# FreshPal_Schematic.net
KiCad netlist of a schematic drawn in Altium Designer
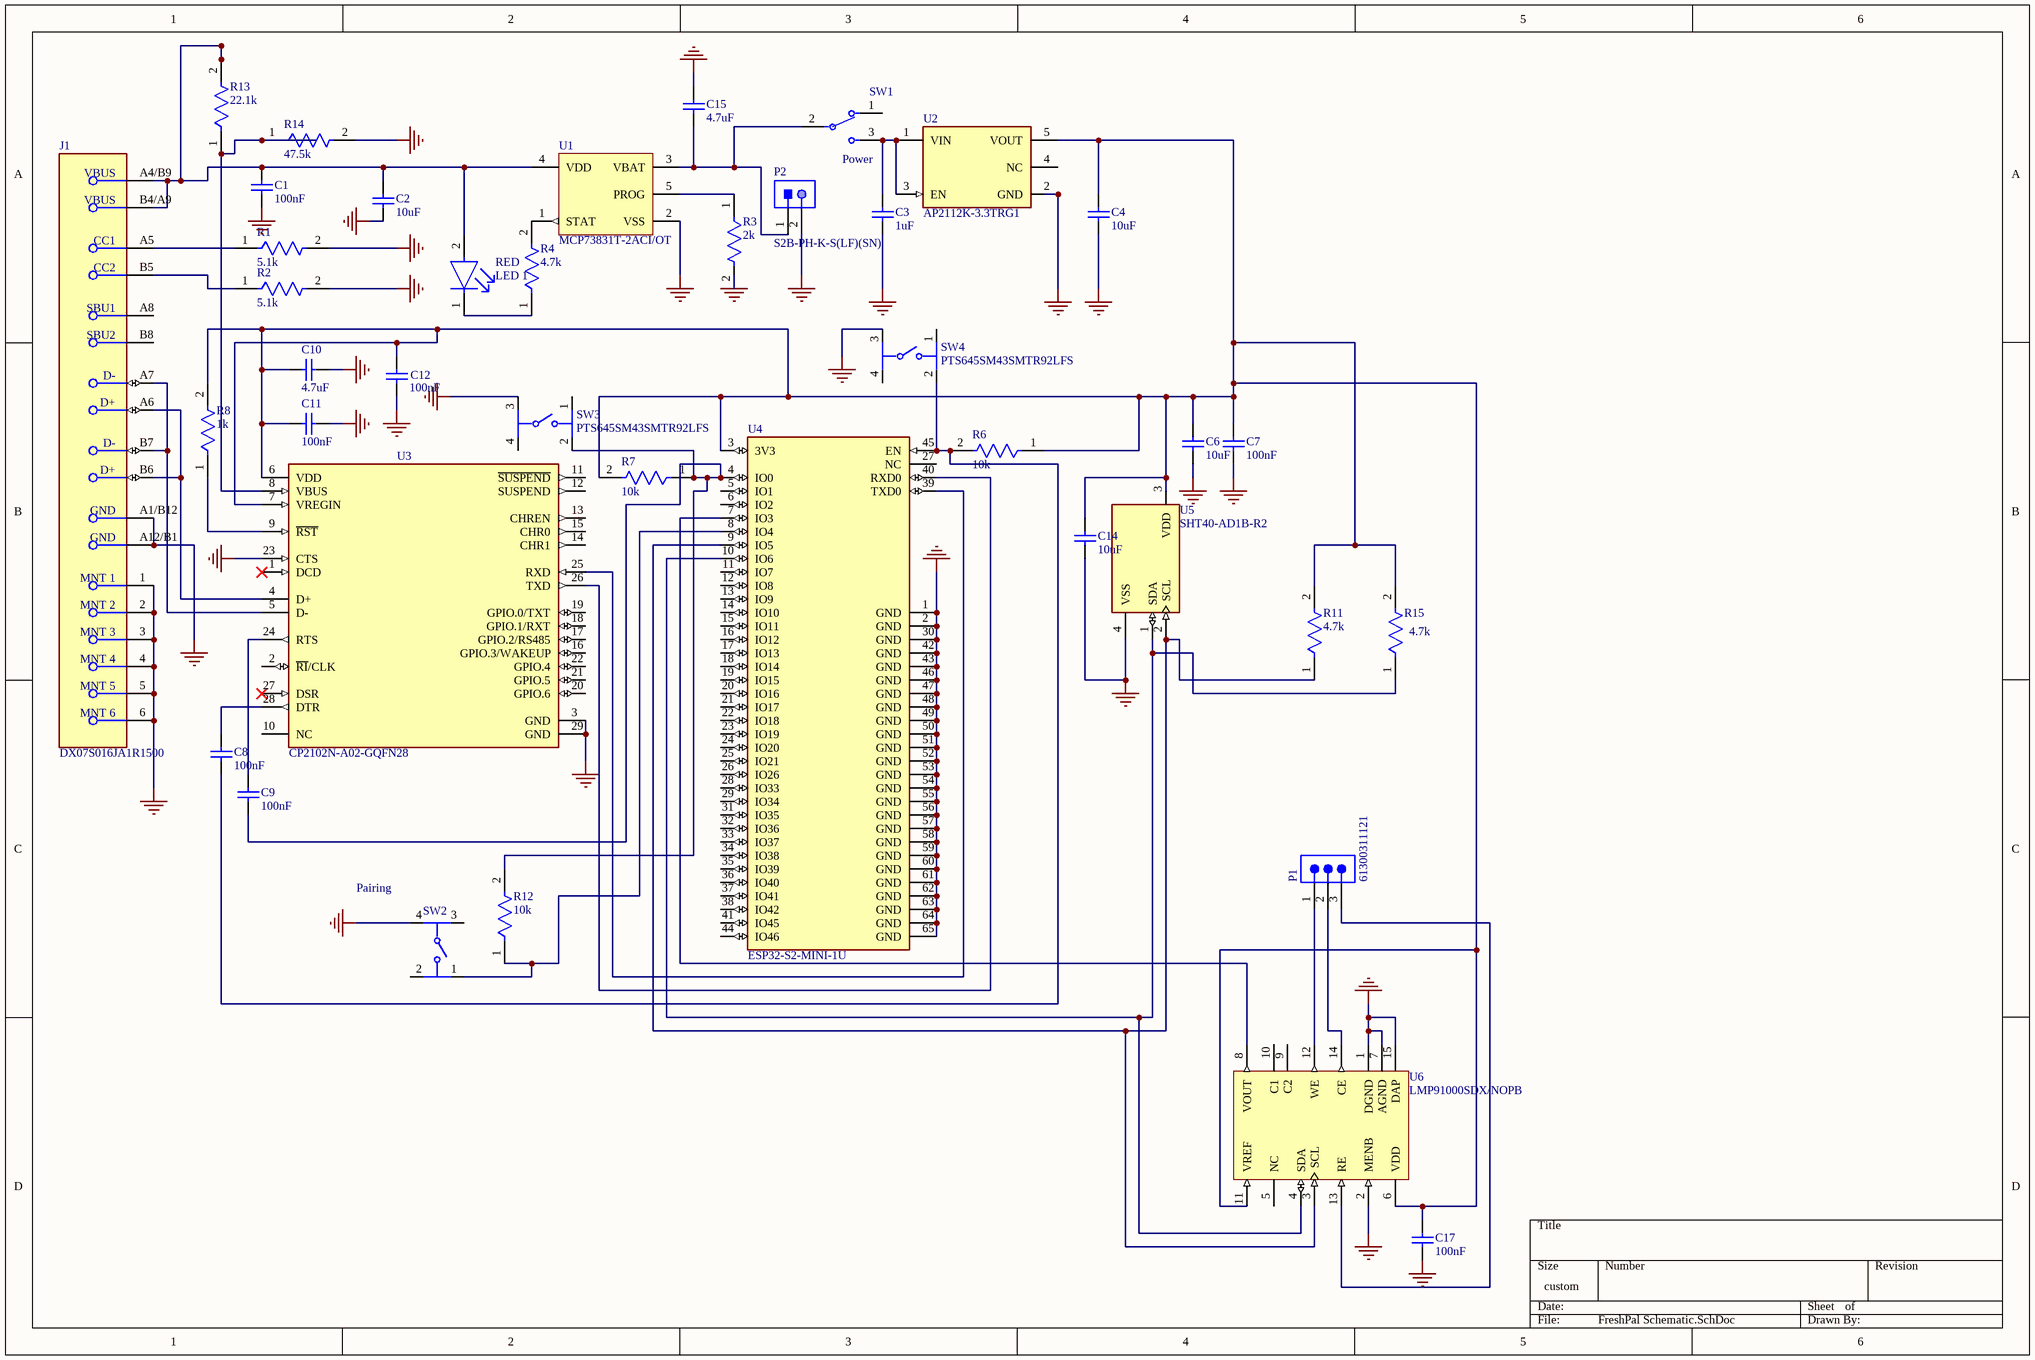
[diagram p0: FreshPal Schematic.SchDoc]

(export (version "E")
  (design (tool "Eeschema 10.0.6"))
  (components
    (comp (ref "C1")
      (value "100nF")
      (footprint "CAPC0603(1608)100_L")
      (description "CAP 3.3pF 16V ±0.1pF 0603 (1608 Metric) Thickness 1mm SMD")
      (fields (field (name "TOLERANCE") "Â±0.1pF"))
      (libsource (lib "Altium Content Vault") (part "CAP"))
    )
    (comp (ref "C2")
      (value "10uF")
      (footprint "CAPC0603(1608)100_L")
      (description "CAP 3.3pF 16V ±0.1pF 0603 (1608 Metric) Thickness 1mm SMD")
      (fields (field (name "TOLERANCE") "Â±0.1pF"))
      (libsource (lib "Altium Content Vault") (part "CAP"))
    )
    (comp (ref "C3")
      (value "1uF")
      (footprint "CAPC0603(1608)100_L")
      (description "CAP 3.3pF 16V ±0.1pF 0603 (1608 Metric) Thickness 1mm SMD")
      (fields (field (name "TOLERANCE") "Â±0.1pF"))
      (libsource (lib "Altium Content Vault") (part "CAP"))
    )
    (comp (ref "C4")
      (value "10uF")
      (footprint "CAPC0603(1608)100_L")
      (description "CAP 3.3pF 16V ±0.1pF 0603 (1608 Metric) Thickness 1mm SMD")
      (fields (field (name "TOLERANCE") "Â±0.1pF"))
      (libsource (lib "Altium Content Vault") (part "CAP"))
    )
    (comp (ref "C6")
      (value "10uF")
      (footprint "CAPC0603(1608)100_L")
      (description "CAP 3.3pF 16V ±0.1pF 0603 (1608 Metric) Thickness 1mm SMD")
      (fields (field (name "TOLERANCE") "Â±0.1pF"))
      (libsource (lib "Altium Content Vault") (part "CAP"))
    )
    (comp (ref "C7")
      (value "100nF")
      (footprint "CAPC0603(1608)100_L")
      (description "CAP 3.3pF 16V ±0.1pF 0603 (1608 Metric) Thickness 1mm SMD")
      (fields (field (name "TOLERANCE") "Â±0.1pF"))
      (libsource (lib "Altium Content Vault") (part "CAP"))
    )
    (comp (ref "C8")
      (value "100nF")
      (footprint "CAPC0603(1608)100_L")
      (description "CAP 3.3pF 16V ±0.1pF 0603 (1608 Metric) Thickness 1mm SMD")
      (fields (field (name "TOLERANCE") "Â±0.1pF"))
      (libsource (lib "Altium Content Vault") (part "CAP"))
    )
    (comp (ref "C9")
      (value "100nF")
      (footprint "CAPC0603(1608)100_L")
      (description "CAP 3.3pF 16V ±0.1pF 0603 (1608 Metric) Thickness 1mm SMD")
      (fields (field (name "TOLERANCE") "Â±0.1pF"))
      (libsource (lib "Altium Content Vault") (part "CAP"))
    )
    (comp (ref "C10")
      (value "4.7uF")
      (footprint "CAPC0603(1608)100_L")
      (description "CAP 3.3pF 16V ±0.1pF 0603 (1608 Metric) Thickness 1mm SMD")
      (fields (field (name "TOLERANCE") "Â±0.1pF"))
      (libsource (lib "Altium Content Vault") (part "CAP"))
    )
    (comp (ref "C11")
      (value "100nF")
      (footprint "CAPC0603(1608)100_L")
      (description "CAP 3.3pF 16V ±0.1pF 0603 (1608 Metric) Thickness 1mm SMD")
      (fields (field (name "TOLERANCE") "Â±0.1pF"))
      (libsource (lib "Altium Content Vault") (part "CAP"))
    )
    (comp (ref "C12")
      (value "100nF")
      (footprint "CAPC0603(1608)100_L")
      (description "CAP 3.3pF 16V ±0.1pF 0603 (1608 Metric) Thickness 1mm SMD")
      (fields (field (name "TOLERANCE") "Â±0.1pF"))
      (libsource (lib "Altium Content Vault") (part "CAP"))
    )
    (comp (ref "C14")
      (value "10uF")
      (footprint "CAPC0603(1608)100_L")
      (description "CAP 3.3pF 16V ±0.1pF 0603 (1608 Metric) Thickness 1mm SMD")
      (fields (field (name "TOLERANCE") "Â±0.1pF"))
      (libsource (lib "Altium Content Vault") (part "CAP"))
    )
    (comp (ref "C15")
      (value "4.7uF")
      (footprint "CAPC0603(1608)100_L")
      (description "CAP 3.3pF 16V ±0.1pF 0603 (1608 Metric) Thickness 1mm SMD")
      (fields (field (name "TOLERANCE") "Â±0.1pF"))
      (libsource (lib "Altium Content Vault") (part "CAP"))
    )
    (comp (ref "C17")
      (value "100nF")
      (footprint "CAPC0603(1608)100_L")
      (description "CAP 3.3pF 16V ±0.1pF 0603 (1608 Metric) Thickness 1mm SMD")
      (fields (field (name "TOLERANCE") "Â±0.1pF"))
      (libsource (lib "Altium Content Vault") (part "CAP"))
    )
    (comp (ref "J1")
      (value "DX07S016JA1R1500")
      (footprint "FP-DX07S016JA1R1500-MFG")
      (description "CONN RCP USB2.0 TYP C 24P SMD RA")
      (libsource (lib "Altium Content Vault") (part "7f3e9989102a0f22bff9cb010881d34"))
    )
    (comp (ref "P1")
      (value "61300311121")
      (footprint "61300311121")
      (description "THT Vertical Pin Header WR-PHD, Pitch 2.54 mm, Single Row, 3 pins")
      (libsource (lib "Altium Content Vault") (part "Header_Male_1R_03P"))
    )
    (comp (ref "P2")
      (value "S2B-PH-K-S(LF)(SN)")
      (footprint "JST-S2B-PH-K-S_V")
      (fields (field (name "TOLERANCE") "20%"))
      (libsource (lib "Altium Content Vault") (part "CN-1P-M-R2"))
    )
    (comp (ref "R1")
      (value "5.1k")
      (footprint "FP-RN73R1E-MFG")
      (description "5.1kΩ ±0.5% 0.063W, 1/16W Chip Resistor 0402 (1005 Metric) Moisture Resistant Thin Film")
      (libsource (lib "Altium Content Vault") (part "1029c3af85768c4190bb7ad29bc67b5"))
    )
    (comp (ref "R2")
      (value "5.1k")
      (footprint "FP-RN73R1E-MFG")
      (description "5.1kΩ ±0.5% 0.063W, 1/16W Chip Resistor 0402 (1005 Metric) Moisture Resistant Thin Film")
      (libsource (lib "Altium Content Vault") (part "1029c3af85768c4190bb7ad29bc67b5"))
    )
    (comp (ref "R3")
      (value "2k")
      (footprint "FP-RN73R1E-IPC_B")
      (description "2kΩ ±1% 0.063W, 1/16W Chip Resistor 0402 (1005 Metric) Moisture Resistant Thin Film")
      (libsource (lib "Altium Content Vault") (part "1029c3af85768c4190bb7ad29bc67b5"))
    )
    (comp (ref "R4")
      (value "4.7k")
      (footprint "FP-RN73R1E-MFG")
      (description "5.1kΩ ±0.5% 0.063W, 1/16W Chip Resistor 0402 (1005 Metric) Moisture Resistant Thin Film")
      (libsource (lib "Altium Content Vault") (part "1029c3af85768c4190bb7ad29bc67b5"))
    )
    (comp (ref "R6")
      (value "10k")
      (footprint "FP-RN73R1E-MFG")
      (description "5.1kΩ ±0.5% 0.063W, 1/16W Chip Resistor 0402 (1005 Metric) Moisture Resistant Thin Film")
      (libsource (lib "Altium Content Vault") (part "1029c3af85768c4190bb7ad29bc67b5"))
    )
    (comp (ref "R7")
      (value "10k")
      (footprint "FP-RN73R1E-MFG")
      (description "5.1kΩ ±0.5% 0.063W, 1/16W Chip Resistor 0402 (1005 Metric) Moisture Resistant Thin Film")
      (libsource (lib "Altium Content Vault") (part "1029c3af85768c4190bb7ad29bc67b5"))
    )
    (comp (ref "R8")
      (value "1k")
      (footprint "FP-RN73R1E-MFG")
      (description "5.1kΩ ±0.5% 0.063W, 1/16W Chip Resistor 0402 (1005 Metric) Moisture Resistant Thin Film")
      (libsource (lib "Altium Content Vault") (part "1029c3af85768c4190bb7ad29bc67b5"))
    )
    (comp (ref "R11")
      (value "4.7k")
      (footprint "FP-RN73R1E-MFG")
      (description "5.1kΩ ±0.5% 0.063W, 1/16W Chip Resistor 0402 (1005 Metric) Moisture Resistant Thin Film")
      (libsource (lib "Altium Content Vault") (part "1029c3af85768c4190bb7ad29bc67b5"))
    )
    (comp (ref "R12")
      (value "10k")
      (footprint "FP-RN73R1E-MFG")
      (description "5.1kΩ ±0.5% 0.063W, 1/16W Chip Resistor 0402 (1005 Metric) Moisture Resistant Thin Film")
      (libsource (lib "Altium Content Vault") (part "1029c3af85768c4190bb7ad29bc67b5"))
    )
    (comp (ref "R13")
      (value "22.1k")
      (footprint "FP-RN73R1E-MFG")
      (description "5.1kΩ ±0.5% 0.063W, 1/16W Chip Resistor 0402 (1005 Metric) Moisture Resistant Thin Film")
      (libsource (lib "Altium Content Vault") (part "1029c3af85768c4190bb7ad29bc67b5"))
    )
    (comp (ref "R14")
      (value "47.5k")
      (footprint "FP-RN732A-MFG")
      (description "SMD Chip Resistor, Thin Film, 69.8KΩ, 100 V, 0805 [2012 Metric], 100 mW, 0.1%, RN73 Series")
      (fields
        (field (name "OCTOPART") "https://octopart.com/rn73c2a69k8btdf-te+connectivity-42431909")
        (field (name "TOLERANCE") "0.1%")
      )
      (libsource (lib "Altium Content Vault") (part "1029c3af85768c4190bb7ad29bc67b5"))
    )
    (comp (ref "R15")
      (value "4.7k")
      (footprint "FP-RN73R1E-MFG")
      (description "5.1kΩ ±0.5% 0.063W, 1/16W Chip Resistor 0402 (1005 Metric) Moisture Resistant Thin Film")
      (libsource (lib "Altium Content Vault") (part "1029c3af85768c4190bb7ad29bc67b5"))
    )
    (comp (ref "RED")
      (value "LED 1")
      (footprint "FP-SML-P1-MFG")
      (description "LED RED CLEAR 1006 SMD")
      (fields
        (field (name "MANUFACTURER PART NUMBER") "SML-P11VTT86R")
        (field (name "OCTOPART") "https://octopart.com/sml-p11vtt86r-rohm-34112314")
      )
      (libsource (lib "Altium Content Vault") (part "8706943c75ba83719d021d2fdc84c58"))
    )
    (comp (ref "SW1")
      (value "S102011SCQN")
      (footprint "FP-JS102011SCQN-MFG")
      (description "SWITCH SLIDE SPDT 300MA 6V")
      (libsource (lib "Altium Content Vault") (part "39e195cbbadc85d1df0d7eb6847d379"))
    )
    (comp (ref "SW2")
      (value "~")
      (footprint "PTS645SM43SMTR92LFS_MFG")
      (description "Switch Tactile N.O SPST Round Button Gull Wing 0.05A 12VDC 100000Cycle 1.57N SMD T/R")
      (libsource (lib "Altium Content Vault") (part "e4f2503661fe04264f50fb928c13ad2"))
    )
    (comp (ref "SW3")
      (value "PTS645SM43SMTR92LFS")
      (footprint "PTS645SM43SMTR92LFS_MFG")
      (description "Switch Tactile N.O SPST Round Button Gull Wing 0.05A 12VDC 100000Cycle 1.57N SMD T/R")
      (libsource (lib "Altium Content Vault") (part "e4f2503661fe04264f50fb928c13ad2"))
    )
    (comp (ref "SW4")
      (value "PTS645SM43SMTR92LFS")
      (footprint "PTS645SM43SMTR92LFS_MFG")
      (description "Switch Tactile N.O SPST Round Button Gull Wing 0.05A 12VDC 100000Cycle 1.57N SMD T/R")
      (libsource (lib "Altium Content Vault") (part "e4f2503661fe04264f50fb928c13ad2"))
    )
    (comp (ref "U1")
      (value "MCP73831T-2ACI/OT")
      (footprint "SOT-23-OT5_M")
      (libsource (lib "Altium Content Vault") (part "PM-BM-MCP73831-SOT5"))
    )
    (comp (ref "U2")
      (value "AP2112K-3.3TRG1")
      (footprint "FP-SOT25-IPC_A")
      (description "IC REG LINEAR 3.3V 600MA SOT25")
      (libsource (lib "Altium Content Vault") (part "c8ab751aee5229183125ab046a11caa"))
    )
    (comp (ref "U3")
      (value "CP2102N-A02-GQFN28")
      (footprint "FP-CP2102N-A02-GQFN28-MFG")
      (description "IC USB TO UART BRIDGE QFN28")
      (libsource (lib "Altium Content Vault") (part "f8fb43f618a03b32512863a7a8093b6"))
    )
    (comp (ref "U4")
      (value "ESP32-S2-MINI-1U")
      (footprint "FP-ESP32-S2-MINI-1U-MFG")
      (description "SMD MODULE W/IPEX ANT CONNECTOR")
      (libsource (lib "Altium Content Vault") (part "b17bfe2a4bfe463d2e3154ec79c1168"))
    )
    (comp (ref "U5")
      (value "SHT40-AD1B-R2")
      (footprint "FP-SHT40-AD1B-R2-MFG")
      (description "SENSOR HUMIDITY 100 RH SMD")
      (libsource (lib "Altium Content Vault") (part "985d6b895d3abb4f56b1b691ea450a8"))
    )
    (comp (ref "U6")
      (value "LMP91000SDX/NOPB")
      (footprint "NHL0014B_V")
      (description "Configurable AFE Potentiostat for Low-Power Chemical Sensing Applications, 14-pin LLP, 4500 Reel")
      (fields (field (name "MANUFACTURER") "Texas Instruments"))
      (libsource (lib "Altium Content Vault") (part "SEN-ELECHEM-LMP91000-15"))
    )
  )
  (nets
    (net (code "1") (name "GND") (class "Default")
      (node (ref "C1") (pin "2") (pinfunction "2_2") (pintype "passive"))
      (node (ref "C10") (pin "2") (pinfunction "2_2") (pintype "passive"))
      (node (ref "C11") (pin "2") (pinfunction "2_2") (pintype "passive"))
      (node (ref "C12") (pin "1") (pinfunction "1_1") (pintype "passive"))
      (node (ref "C14") (pin "2") (pinfunction "2_2") (pintype "passive"))
      (node (ref "C15") (pin "1") (pinfunction "1_1") (pintype "passive"))
      (node (ref "C17") (pin "1") (pinfunction "1_1") (pintype "passive"))
      (node (ref "C2") (pin "2") (pinfunction "2_2") (pintype "passive"))
      (node (ref "C3") (pin "2") (pinfunction "2_2") (pintype "passive"))
      (node (ref "C4") (pin "2") (pinfunction "2_2") (pintype "passive"))
      (node (ref "C6") (pin "2") (pinfunction "2_2") (pintype "passive"))
      (node (ref "C7") (pin "2") (pinfunction "2_2") (pintype "passive"))
      (node (ref "J1") (pin "1") (pinfunction "MNT_1_1") (pintype "passive"))
      (node (ref "J1") (pin "2") (pinfunction "MNT_2_2") (pintype "passive"))
      (node (ref "J1") (pin "3") (pinfunction "MNT_3_3") (pintype "passive"))
      (node (ref "J1") (pin "4") (pinfunction "MNT_4_4") (pintype "passive"))
      (node (ref "J1") (pin "5") (pinfunction "MNT_5_5") (pintype "passive"))
      (node (ref "J1") (pin "6") (pinfunction "MNT_6_6") (pintype "passive"))
      (node (ref "J1") (pin "A1/B12") (pinfunction "GND_A1/B12") (pintype "power_in"))
      (node (ref "J1") (pin "A12/B1") (pinfunction "GND_A12/B1") (pintype "power_in"))
      (node (ref "P2") (pin "2") (pinfunction "2_2") (pintype "passive"))
      (node (ref "R1") (pin "2") (pinfunction "2_2") (pintype "passive"))
      (node (ref "R14") (pin "2") (pinfunction "2_2") (pintype "passive"))
      (node (ref "R2") (pin "2") (pinfunction "2_2") (pintype "passive"))
      (node (ref "R3") (pin "2") (pinfunction "2_2") (pintype "passive"))
      (node (ref "SW2") (pin "4") (pinfunction "4_4") (pintype "passive"))
      (node (ref "SW3") (pin "3") (pinfunction "3_3") (pintype "passive"))
      (node (ref "SW4") (pin "3") (pinfunction "3_3") (pintype "passive"))
      (node (ref "U1") (pin "2") (pinfunction "VSS_2") (pintype "power_in"))
      (node (ref "U2") (pin "2") (pinfunction "GND_2") (pintype "power_in"))
      (node (ref "U3") (pin "23") (pinfunction "CTS_23") (pintype "input"))
      (node (ref "U3") (pin "29") (pinfunction "GND_29") (pintype "power_in"))
      (node (ref "U3") (pin "3") (pinfunction "GND_3") (pintype "power_in"))
      (node (ref "U4") (pin "1") (pinfunction "GND_1") (pintype "power_in"))
      (node (ref "U4") (pin "2") (pinfunction "GND_2") (pintype "power_in"))
      (node (ref "U4") (pin "30") (pinfunction "GND_30") (pintype "power_in"))
      (node (ref "U4") (pin "42") (pinfunction "GND_42") (pintype "power_in"))
      (node (ref "U4") (pin "43") (pinfunction "GND_43") (pintype "power_in"))
      (node (ref "U4") (pin "46") (pinfunction "GND_46") (pintype "power_in"))
      (node (ref "U4") (pin "47") (pinfunction "GND_47") (pintype "power_in"))
      (node (ref "U4") (pin "48") (pinfunction "GND_48") (pintype "power_in"))
      (node (ref "U4") (pin "49") (pinfunction "GND_49") (pintype "power_in"))
      (node (ref "U4") (pin "50") (pinfunction "GND_50") (pintype "power_in"))
      (node (ref "U4") (pin "51") (pinfunction "GND_51") (pintype "power_in"))
      (node (ref "U4") (pin "52") (pinfunction "GND_52") (pintype "power_in"))
      (node (ref "U4") (pin "53") (pinfunction "GND_53") (pintype "power_in"))
      (node (ref "U4") (pin "54") (pinfunction "GND_54") (pintype "power_in"))
      (node (ref "U4") (pin "55") (pinfunction "GND_55") (pintype "power_in"))
      (node (ref "U4") (pin "56") (pinfunction "GND_56") (pintype "power_in"))
      (node (ref "U4") (pin "57") (pinfunction "GND_57") (pintype "power_in"))
      (node (ref "U4") (pin "58") (pinfunction "GND_58") (pintype "power_in"))
      (node (ref "U4") (pin "59") (pinfunction "GND_59") (pintype "power_in"))
      (node (ref "U4") (pin "60") (pinfunction "GND_60") (pintype "power_in"))
      (node (ref "U4") (pin "61") (pinfunction "GND_61") (pintype "power_in"))
      (node (ref "U4") (pin "62") (pinfunction "GND_62") (pintype "power_in"))
      (node (ref "U4") (pin "63") (pinfunction "GND_63") (pintype "power_in"))
      (node (ref "U4") (pin "64") (pinfunction "GND_64") (pintype "power_in"))
      (node (ref "U4") (pin "65") (pinfunction "GND_65") (pintype "power_in"))
      (node (ref "U5") (pin "4") (pinfunction "VSS_4") (pintype "power_in"))
      (node (ref "U6") (pin "1") (pinfunction "DGND_1") (pintype "power_in"))
      (node (ref "U6") (pin "15") (pinfunction "DAP_15") (pintype "power_in"))
      (node (ref "U6") (pin "2") (pinfunction "MENB_2") (pintype "input"))
      (node (ref "U6") (pin "7") (pinfunction "AGND_7") (pintype "power_in"))
    )
    (net (code "2") (name "Net-(J1-CC1)") (class "Default")
      (node (ref "J1") (pin "A5") (pinfunction "CC1_A5") (pintype "passive"))
      (node (ref "R1") (pin "1") (pinfunction "1_1") (pintype "passive"))
    )
    (net (code "3") (name "Net-(J1-CC2)") (class "Default")
      (node (ref "J1") (pin "B5") (pinfunction "CC2_B5") (pintype "passive"))
      (node (ref "R2") (pin "1") (pinfunction "1_1") (pintype "passive"))
    )
    (net (code "4") (name "Net-(RED-A)") (class "Default")
      (node (ref "C1") (pin "1") (pinfunction "1_1") (pintype "passive"))
      (node (ref "C2") (pin "1") (pinfunction "1_1") (pintype "passive"))
      (node (ref "J1") (pin "A4/B9") (pinfunction "VBUS_A4/B9") (pintype "power_in"))
      (node (ref "J1") (pin "B4/A9") (pinfunction "VBUS_B4/A9") (pintype "power_in"))
      (node (ref "R13") (pin "2") (pinfunction "2_2") (pintype "passive"))
      (node (ref "RED") (pin "2") (pinfunction "A_2") (pintype "passive"))
      (node (ref "U1") (pin "4") (pinfunction "VDD_4") (pintype "power_in"))
    )
    (net (code "5") (name "Net-(RED-C)") (class "Default")
      (node (ref "R4") (pin "1") (pinfunction "1_1") (pintype "passive"))
      (node (ref "RED") (pin "1") (pinfunction "C_1") (pintype "passive"))
    )
    (net (code "6") (name "Net-(SW1-C)") (class "Default")
      (node (ref "C15") (pin "2") (pinfunction "2_2") (pintype "passive"))
      (node (ref "P2") (pin "1") (pinfunction "1_1") (pintype "passive"))
      (node (ref "SW1") (pin "2") (pinfunction "C_2") (pintype "passive"))
      (node (ref "U1") (pin "3") (pinfunction "VBAT_3") (pintype "power_in"))
    )
    (net (code "7") (name "Net-(U1-PROG)") (class "Default")
      (node (ref "R3") (pin "1") (pinfunction "1_1") (pintype "passive"))
      (node (ref "U1") (pin "5") (pinfunction "PROG_5") (pintype "passive"))
    )
    (net (code "8") (name "Net-(U1-STAT)") (class "Default")
      (node (ref "R4") (pin "2") (pinfunction "2_2") (pintype "passive"))
      (node (ref "U1") (pin "1") (pinfunction "STAT_1") (pintype "output"))
    )
    (net (code "9") (name "Net-(U2-EN)") (class "Default")
      (node (ref "C3") (pin "1") (pinfunction "1_1") (pintype "passive"))
      (node (ref "SW1") (pin "3") (pinfunction "3_3") (pintype "passive"))
      (node (ref "U2") (pin "1") (pinfunction "VIN_1") (pintype "power_in"))
      (node (ref "U2") (pin "3") (pinfunction "EN_3") (pintype "input"))
    )
    (net (code "10") (name "Net-(U2-VOUT)") (class "Default")
      (node (ref "C10") (pin "1") (pinfunction "1_1") (pintype "passive"))
      (node (ref "C11") (pin "1") (pinfunction "1_1") (pintype "passive"))
      (node (ref "C12") (pin "2") (pinfunction "2_2") (pintype "passive"))
      (node (ref "C14") (pin "1") (pinfunction "1_1") (pintype "passive"))
      (node (ref "C17") (pin "2") (pinfunction "2_2") (pintype "passive"))
      (node (ref "C4") (pin "1") (pinfunction "1_1") (pintype "passive"))
      (node (ref "C6") (pin "1") (pinfunction "1_1") (pintype "passive"))
      (node (ref "C7") (pin "1") (pinfunction "1_1") (pintype "passive"))
      (node (ref "R11") (pin "2") (pinfunction "2_2") (pintype "passive"))
      (node (ref "R15") (pin "2") (pinfunction "2_2") (pintype "passive"))
      (node (ref "R6") (pin "1") (pinfunction "1_1") (pintype "passive"))
      (node (ref "R7") (pin "2") (pinfunction "2_2") (pintype "passive"))
      (node (ref "R8") (pin "2") (pinfunction "2_2") (pintype "passive"))
      (node (ref "U2") (pin "5") (pinfunction "VOUT_5") (pintype "power_in"))
      (node (ref "U3") (pin "6") (pinfunction "VDD_6") (pintype "power_in"))
      (node (ref "U3") (pin "7") (pinfunction "VREGIN_7") (pintype "input"))
      (node (ref "U4") (pin "3") (pinfunction "3V3_3") (pintype "bidirectional"))
      (node (ref "U5") (pin "3") (pinfunction "VDD_3") (pintype "power_in"))
      (node (ref "U6") (pin "11") (pinfunction "VREF_11") (pintype "input"))
      (node (ref "U6") (pin "6") (pinfunction "VDD_6") (pintype "power_in"))
    )
    (net (code "11") (name "Net-(U3-D+)") (class "Default")
      (node (ref "J1") (pin "A6") (pinfunction "D+_A6") (pintype "bidirectional"))
      (node (ref "J1") (pin "B6") (pinfunction "D+_B6") (pintype "bidirectional"))
      (node (ref "U3") (pin "4") (pinfunction "D+_4") (pintype "passive"))
    )
    (net (code "12") (name "Net-(U3-D-)") (class "Default")
      (node (ref "J1") (pin "A7") (pinfunction "D-_A7") (pintype "bidirectional"))
      (node (ref "J1") (pin "B7") (pinfunction "D-_B7") (pintype "bidirectional"))
      (node (ref "U3") (pin "5") (pinfunction "D-_5") (pintype "passive"))
    )
    (net (code "13") (name "Net-(U3-DTR)") (class "Default")
      (node (ref "C8") (pin "2") (pinfunction "2_2") (pintype "passive"))
      (node (ref "U3") (pin "28") (pinfunction "DTR_28") (pintype "output"))
    )
    (net (code "14") (name "Net-(U3-RTS)") (class "Default")
      (node (ref "C9") (pin "2") (pinfunction "2_2") (pintype "passive"))
      (node (ref "U3") (pin "24") (pinfunction "RTS_24") (pintype "output"))
    )
    (net (code "15") (name "Net-(U3-RXD)") (class "Default")
      (node (ref "U3") (pin "25") (pinfunction "RXD_25") (pintype "input"))
      (node (ref "U4") (pin "39") (pinfunction "TXD0_39") (pintype "bidirectional"))
    )
    (net (code "16") (name "Net-(U3-TXD)") (class "Default")
      (node (ref "U3") (pin "26") (pinfunction "TXD_26") (pintype "output"))
      (node (ref "U4") (pin "40") (pinfunction "RXD0_40") (pintype "bidirectional"))
    )
    (net (code "17") (name "Net-(U3-VBUS)") (class "Default")
      (node (ref "R13") (pin "1") (pinfunction "1_1") (pintype "passive"))
      (node (ref "R14") (pin "1") (pinfunction "1_1") (pintype "passive"))
      (node (ref "U3") (pin "8") (pinfunction "VBUS_8") (pintype "input"))
    )
    (net (code "18") (name "Net-(U3-~{RST})") (class "Default")
      (node (ref "R8") (pin "1") (pinfunction "1_1") (pintype "passive"))
      (node (ref "U3") (pin "9") (pinfunction "~{RST}_9") (pintype "input"))
    )
    (net (code "19") (name "Net-(U4-EN)") (class "Default")
      (node (ref "C8") (pin "1") (pinfunction "1_1") (pintype "passive"))
      (node (ref "R6") (pin "2") (pinfunction "2_2") (pintype "passive"))
      (node (ref "SW4") (pin "2") (pinfunction "2_2") (pintype "passive"))
      (node (ref "U4") (pin "45") (pinfunction "EN_45") (pintype "input"))
    )
    (net (code "20") (name "Net-(U4-IO0)") (class "Default")
      (node (ref "C9") (pin "1") (pinfunction "1_1") (pintype "passive"))
      (node (ref "R12") (pin "2") (pinfunction "2_2") (pintype "passive"))
      (node (ref "R7") (pin "1") (pinfunction "1_1") (pintype "passive"))
      (node (ref "SW3") (pin "2") (pinfunction "2_2") (pintype "passive"))
      (node (ref "U4") (pin "4") (pinfunction "IO0_4") (pintype "bidirectional"))
    )
    (net (code "21") (name "Net-(U4-IO3)") (class "Default")
      (node (ref "U4") (pin "7") (pinfunction "IO3_7") (pintype "bidirectional"))
      (node (ref "U6") (pin "8") (pinfunction "VOUT_8") (pintype "output"))
    )
    (net (code "22") (name "Net-(U4-IO4)") (class "Default")
      (node (ref "R12") (pin "1") (pinfunction "1_1") (pintype "passive"))
      (node (ref "SW2") (pin "1") (pinfunction "1_1") (pintype "passive"))
      (node (ref "U4") (pin "8") (pinfunction "IO4_8") (pintype "bidirectional"))
    )
    (net (code "23") (name "Net-(U4-IO5)") (class "Default")
      (node (ref "R11") (pin "1") (pinfunction "1_1") (pintype "passive"))
      (node (ref "U4") (pin "9") (pinfunction "IO5_9") (pintype "bidirectional"))
      (node (ref "U5") (pin "2") (pinfunction "SCL_2") (pintype "input"))
      (node (ref "U6") (pin "3") (pinfunction "SCL_3") (pintype "input"))
    )
    (net (code "24") (name "Net-(U4-IO6)") (class "Default")
      (node (ref "R15") (pin "1") (pinfunction "1_1") (pintype "passive"))
      (node (ref "U4") (pin "10") (pinfunction "IO6_10") (pintype "bidirectional"))
      (node (ref "U5") (pin "1") (pinfunction "SDA_1") (pintype "bidirectional"))
      (node (ref "U6") (pin "4") (pinfunction "SDA_4") (pintype "bidirectional"))
    )
    (net (code "25") (name "Net-(U6-CE)") (class "Default")
      (node (ref "P1") (pin "2") (pinfunction "2_2") (pintype "passive"))
      (node (ref "U6") (pin "14") (pinfunction "CE_14") (pintype "output"))
    )
    (net (code "26") (name "Net-(U6-RE)") (class "Default")
      (node (ref "P1") (pin "3") (pinfunction "3_3") (pintype "passive"))
      (node (ref "U6") (pin "13") (pinfunction "RE_13") (pintype "input"))
    )
    (net (code "27") (name "Net-(U6-WE)") (class "Default")
      (node (ref "P1") (pin "1") (pinfunction "1_1") (pintype "passive"))
      (node (ref "U6") (pin "12") (pinfunction "WE_12") (pintype "output"))
    )
    (net (code "28") (name "unconnected-(J1-SBU1-PadA8)") (class "Default")
      (node (ref "J1") (pin "A8") (pinfunction "SBU1_A8") (pintype "passive"))
    )
    (net (code "29") (name "unconnected-(J1-SBU2-PadB8)") (class "Default")
      (node (ref "J1") (pin "B8") (pinfunction "SBU2_B8") (pintype "passive"))
    )
    (net (code "30") (name "unconnected-(SW1-Pad1)") (class "Default")
      (node (ref "SW1") (pin "1") (pinfunction "1_1") (pintype "passive"))
    )
    (net (code "31") (name "unconnected-(SW2-Pad2)") (class "Default")
      (node (ref "SW2") (pin "2") (pinfunction "2_2") (pintype "passive"))
    )
    (net (code "32") (name "unconnected-(SW2-Pad3)") (class "Default")
      (node (ref "SW2") (pin "3") (pinfunction "3_3") (pintype "passive"))
    )
    (net (code "33") (name "unconnected-(SW3-Pad1)") (class "Default")
      (node (ref "SW3") (pin "1") (pinfunction "1_1") (pintype "passive"))
    )
    (net (code "34") (name "unconnected-(SW3-Pad4)") (class "Default")
      (node (ref "SW3") (pin "4") (pinfunction "4_4") (pintype "passive"))
    )
    (net (code "35") (name "unconnected-(SW4-Pad1)") (class "Default")
      (node (ref "SW4") (pin "1") (pinfunction "1_1") (pintype "passive"))
    )
    (net (code "36") (name "unconnected-(SW4-Pad4)") (class "Default")
      (node (ref "SW4") (pin "4") (pinfunction "4_4") (pintype "passive"))
    )
    (net (code "37") (name "unconnected-(U2-NC-Pad4)") (class "Default")
      (node (ref "U2") (pin "4") (pinfunction "NC_4") (pintype "passive"))
    )
    (net (code "38") (name "unconnected-(U3-CHR0-Pad15)") (class "Default")
      (node (ref "U3") (pin "15") (pinfunction "CHR0_15") (pintype "output"))
    )
    (net (code "39") (name "unconnected-(U3-CHR1-Pad14)") (class "Default")
      (node (ref "U3") (pin "14") (pinfunction "CHR1_14") (pintype "output"))
    )
    (net (code "40") (name "unconnected-(U3-CHREN-Pad13)") (class "Default")
      (node (ref "U3") (pin "13") (pinfunction "CHREN_13") (pintype "output"))
    )
    (net (code "41") (name "unconnected-(U3-DCD-Pad1)") (class "Default")
      (node (ref "U3") (pin "1") (pinfunction "DCD_1") (pintype "input+no_connect"))
    )
    (net (code "42") (name "unconnected-(U3-DSR-Pad27)") (class "Default")
      (node (ref "U3") (pin "27") (pinfunction "DSR_27") (pintype "input+no_connect"))
    )
    (net (code "43") (name "unconnected-(U3-GPIO.0{slash}TXT-Pad19)") (class "Default")
      (node (ref "U3") (pin "19") (pinfunction "GPIO.0/TXT_19") (pintype "bidirectional"))
    )
    (net (code "44") (name "unconnected-(U3-GPIO.1{slash}RXT-Pad18)") (class "Default")
      (node (ref "U3") (pin "18") (pinfunction "GPIO.1/RXT_18") (pintype "bidirectional"))
    )
    (net (code "45") (name "unconnected-(U3-GPIO.2{slash}RS485-Pad17)") (class "Default")
      (node (ref "U3") (pin "17") (pinfunction "GPIO.2/RS485_17") (pintype "bidirectional"))
    )
    (net (code "46") (name "unconnected-(U3-GPIO.3{slash}WAKEUP-Pad16)") (class "Default")
      (node (ref "U3") (pin "16") (pinfunction "GPIO.3/WAKEUP_16") (pintype "bidirectional"))
    )
    (net (code "47") (name "unconnected-(U3-GPIO.4-Pad22)") (class "Default")
      (node (ref "U3") (pin "22") (pinfunction "GPIO.4_22") (pintype "bidirectional"))
    )
    (net (code "48") (name "unconnected-(U3-GPIO.5-Pad21)") (class "Default")
      (node (ref "U3") (pin "21") (pinfunction "GPIO.5_21") (pintype "bidirectional"))
    )
    (net (code "49") (name "unconnected-(U3-GPIO.6-Pad20)") (class "Default")
      (node (ref "U3") (pin "20") (pinfunction "GPIO.6_20") (pintype "bidirectional"))
    )
    (net (code "50") (name "unconnected-(U3-NC-Pad10)") (class "Default")
      (node (ref "U3") (pin "10") (pinfunction "NC_10") (pintype "passive"))
    )
    (net (code "51") (name "unconnected-(U3-SUSPEND-Pad12)") (class "Default")
      (node (ref "U3") (pin "12") (pinfunction "SUSPEND_12") (pintype "output"))
    )
    (net (code "52") (name "unconnected-(U3-~{RI}{slash}CLK-Pad2)") (class "Default")
      (node (ref "U3") (pin "2") (pinfunction "~{RI}/CLK_2") (pintype "bidirectional"))
    )
    (net (code "53") (name "unconnected-(U3-~{SUSPEND}-Pad11)") (class "Default")
      (node (ref "U3") (pin "11") (pinfunction "~{SUSPEND}_11") (pintype "output"))
    )
    (net (code "54") (name "unconnected-(U4-IO1-Pad5)") (class "Default")
      (node (ref "U4") (pin "5") (pinfunction "IO1_5") (pintype "bidirectional"))
    )
    (net (code "55") (name "unconnected-(U4-IO2-Pad6)") (class "Default")
      (node (ref "U4") (pin "6") (pinfunction "IO2_6") (pintype "bidirectional"))
    )
    (net (code "56") (name "unconnected-(U4-IO7-Pad11)") (class "Default")
      (node (ref "U4") (pin "11") (pinfunction "IO7_11") (pintype "bidirectional"))
    )
    (net (code "57") (name "unconnected-(U4-IO8-Pad12)") (class "Default")
      (node (ref "U4") (pin "12") (pinfunction "IO8_12") (pintype "bidirectional"))
    )
    (net (code "58") (name "unconnected-(U4-IO9-Pad13)") (class "Default")
      (node (ref "U4") (pin "13") (pinfunction "IO9_13") (pintype "bidirectional"))
    )
    (net (code "59") (name "unconnected-(U4-IO10-Pad14)") (class "Default")
      (node (ref "U4") (pin "14") (pinfunction "IO10_14") (pintype "bidirectional"))
    )
    (net (code "60") (name "unconnected-(U4-IO11-Pad15)") (class "Default")
      (node (ref "U4") (pin "15") (pinfunction "IO11_15") (pintype "bidirectional"))
    )
    (net (code "61") (name "unconnected-(U4-IO12-Pad16)") (class "Default")
      (node (ref "U4") (pin "16") (pinfunction "IO12_16") (pintype "bidirectional"))
    )
    (net (code "62") (name "unconnected-(U4-IO13-Pad17)") (class "Default")
      (node (ref "U4") (pin "17") (pinfunction "IO13_17") (pintype "bidirectional"))
    )
    (net (code "63") (name "unconnected-(U4-IO14-Pad18)") (class "Default")
      (node (ref "U4") (pin "18") (pinfunction "IO14_18") (pintype "bidirectional"))
    )
    (net (code "64") (name "unconnected-(U4-IO15-Pad19)") (class "Default")
      (node (ref "U4") (pin "19") (pinfunction "IO15_19") (pintype "bidirectional"))
    )
    (net (code "65") (name "unconnected-(U4-IO16-Pad20)") (class "Default")
      (node (ref "U4") (pin "20") (pinfunction "IO16_20") (pintype "bidirectional"))
    )
    (net (code "66") (name "unconnected-(U4-IO17-Pad21)") (class "Default")
      (node (ref "U4") (pin "21") (pinfunction "IO17_21") (pintype "bidirectional"))
    )
    (net (code "67") (name "unconnected-(U4-IO18-Pad22)") (class "Default")
      (node (ref "U4") (pin "22") (pinfunction "IO18_22") (pintype "bidirectional"))
    )
    (net (code "68") (name "unconnected-(U4-IO19-Pad23)") (class "Default")
      (node (ref "U4") (pin "23") (pinfunction "IO19_23") (pintype "bidirectional"))
    )
    (net (code "69") (name "unconnected-(U4-IO20-Pad24)") (class "Default")
      (node (ref "U4") (pin "24") (pinfunction "IO20_24") (pintype "bidirectional"))
    )
    (net (code "70") (name "unconnected-(U4-IO21-Pad25)") (class "Default")
      (node (ref "U4") (pin "25") (pinfunction "IO21_25") (pintype "bidirectional"))
    )
    (net (code "71") (name "unconnected-(U4-IO26-Pad26)") (class "Default")
      (node (ref "U4") (pin "26") (pinfunction "IO26_26") (pintype "bidirectional"))
    )
    (net (code "72") (name "unconnected-(U4-IO33-Pad28)") (class "Default")
      (node (ref "U4") (pin "28") (pinfunction "IO33_28") (pintype "bidirectional"))
    )
    (net (code "73") (name "unconnected-(U4-IO34-Pad29)") (class "Default")
      (node (ref "U4") (pin "29") (pinfunction "IO34_29") (pintype "bidirectional"))
    )
    (net (code "74") (name "unconnected-(U4-IO35-Pad31)") (class "Default")
      (node (ref "U4") (pin "31") (pinfunction "IO35_31") (pintype "bidirectional"))
    )
    (net (code "75") (name "unconnected-(U4-IO36-Pad32)") (class "Default")
      (node (ref "U4") (pin "32") (pinfunction "IO36_32") (pintype "bidirectional"))
    )
    (net (code "76") (name "unconnected-(U4-IO37-Pad33)") (class "Default")
      (node (ref "U4") (pin "33") (pinfunction "IO37_33") (pintype "bidirectional"))
    )
    (net (code "77") (name "unconnected-(U4-IO38-Pad34)") (class "Default")
      (node (ref "U4") (pin "34") (pinfunction "IO38_34") (pintype "bidirectional"))
    )
    (net (code "78") (name "unconnected-(U4-IO39-Pad35)") (class "Default")
      (node (ref "U4") (pin "35") (pinfunction "IO39_35") (pintype "bidirectional"))
    )
    (net (code "79") (name "unconnected-(U4-IO40-Pad36)") (class "Default")
      (node (ref "U4") (pin "36") (pinfunction "IO40_36") (pintype "bidirectional"))
    )
    (net (code "80") (name "unconnected-(U4-IO41-Pad37)") (class "Default")
      (node (ref "U4") (pin "37") (pinfunction "IO41_37") (pintype "bidirectional"))
    )
    (net (code "81") (name "unconnected-(U4-IO42-Pad38)") (class "Default")
      (node (ref "U4") (pin "38") (pinfunction "IO42_38") (pintype "bidirectional"))
    )
    (net (code "82") (name "unconnected-(U4-IO45-Pad41)") (class "Default")
      (node (ref "U4") (pin "41") (pinfunction "IO45_41") (pintype "bidirectional"))
    )
    (net (code "83") (name "unconnected-(U4-IO46-Pad44)") (class "Default")
      (node (ref "U4") (pin "44") (pinfunction "IO46_44") (pintype "bidirectional"))
    )
    (net (code "84") (name "unconnected-(U4-NC-Pad27)") (class "Default")
      (node (ref "U4") (pin "27") (pinfunction "NC_27") (pintype "passive"))
    )
    (net (code "85") (name "unconnected-(U6-C1-Pad10)") (class "Default")
      (node (ref "U6") (pin "10") (pinfunction "C1_10") (pintype "passive"))
    )
    (net (code "86") (name "unconnected-(U6-C2-Pad9)") (class "Default")
      (node (ref "U6") (pin "9") (pinfunction "C2_9") (pintype "passive"))
    )
    (net (code "87") (name "unconnected-(U6-NC-Pad5)") (class "Default")
      (node (ref "U6") (pin "5") (pinfunction "NC_5") (pintype "passive"))
    )
  )
)
